# SuperSimpleEMG.net
KiCad netlist of a schematic drawn in EAGLE
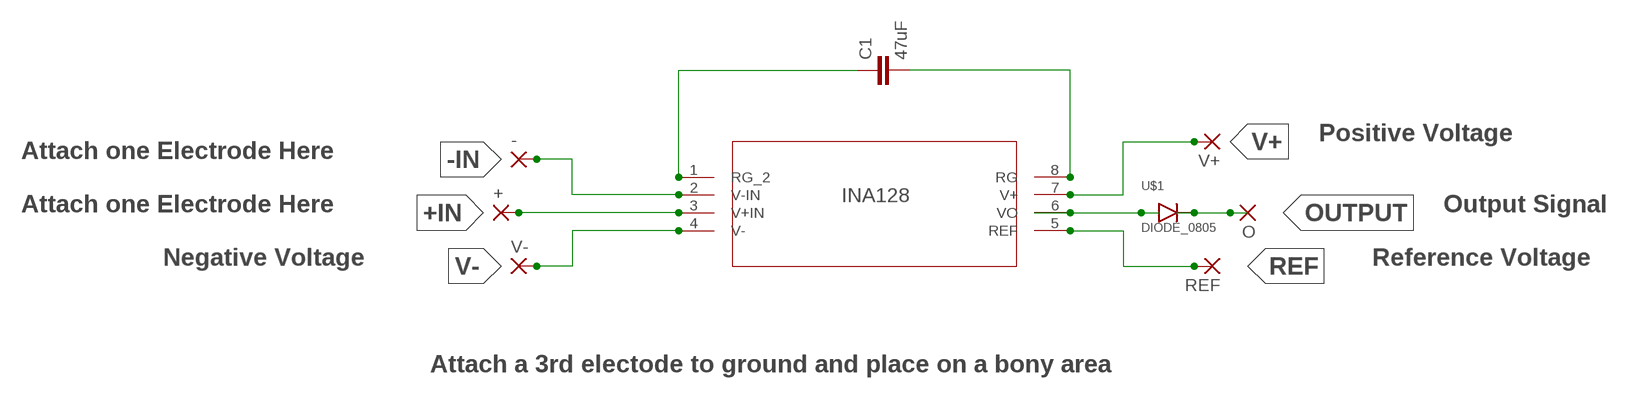
[diagram p0: schematic, sheet 1]

(export (version "E")
  (design (tool "Eeschema 10.0.6"))
  (components
    (comp (ref "+")
      (value "2,15/1,0")
      (footprint "eagle-import:2,15_1,0")
      (libsource (lib "eagle-import") (part "2,15/1,0"))
    )
    (comp (ref "-")
      (value "2,15/1,0")
      (footprint "eagle-import:2,15_1,0")
      (libsource (lib "eagle-import") (part "2,15/1,0"))
    )
    (comp (ref "C1")
      (value "47uF")
      (footprint "eagle-import:0805")
      (fields (field (name "MF") "NICHICON") (field (name "MPN") "F980J476MSA"))
      (libsource (lib "eagle-import") (part "CAP0805"))
    )
    (comp (ref "INA128")
      (value "INA128_D_8")
      (footprint "eagle-import:D8")
      (fields
        (field (name "GENERIC_PART_NUMBER") "INA128")
        (field (name "MANUFACTURER") "Texas Instruments")
        (field (name "MANUFACTURER_PART_NUMBER") "ina128_d_8")
      )
      (libsource (lib "eagle-import") (part "INA128_D_8"))
    )
    (comp (ref "O")
      (value "2,15/1,0")
      (footprint "eagle-import:2,15_1,0")
      (libsource (lib "eagle-import") (part "2,15/1,0"))
    )
    (comp (ref "REF")
      (value "2,15/1,0")
      (footprint "eagle-import:2,15_1,0")
      (libsource (lib "eagle-import") (part "2,15/1,0"))
    )
    (comp (ref "U$1")
      (value "DIODE_0805")
      (footprint "eagle-import:DIODE_0805")
      (libsource (lib "eagle-import") (part "DIODE_0805"))
    )
    (comp (ref "V+")
      (value "2,15/1,0")
      (footprint "eagle-import:2,15_1,0")
      (libsource (lib "eagle-import") (part "2,15/1,0"))
    )
    (comp (ref "V-")
      (value "2,15/1,0")
      (footprint "eagle-import:2,15_1,0")
      (libsource (lib "eagle-import") (part "2,15/1,0"))
    )
  )
  (nets
    (net (code "1") (name "+IN") (class "Default")
      (node (ref "+") (pin "1") (pinfunction "P_1") (pintype "passive"))
      (node (ref "INA128") (pin "3") (pinfunction "V+IN_3") (pintype "input"))
    )
    (net (code "2") (name "-IN") (class "Default")
      (node (ref "-") (pin "1") (pinfunction "P_1") (pintype "passive"))
      (node (ref "INA128") (pin "2") (pinfunction "V-IN_2") (pintype "input"))
    )
    (net (code "3") (name "Net-(INA128-RG)") (class "Default")
      (node (ref "C1") (pin "2") (pinfunction "2_2") (pintype "passive"))
      (node (ref "INA128") (pin "8") (pinfunction "RG_8") (pintype "passive"))
    )
    (net (code "4") (name "Net-(INA128-RG_2)") (class "Default")
      (node (ref "C1") (pin "1") (pinfunction "1_1") (pintype "passive"))
      (node (ref "INA128") (pin "1") (pinfunction "RG_2_1") (pintype "passive"))
    )
    (net (code "5") (name "Net-(INA128-VO)") (class "Default")
      (node (ref "INA128") (pin "6") (pinfunction "VO_6") (pintype "output"))
      (node (ref "U$1") (pin "A") (pinfunction "A_A") (pintype "passive"))
    )
    (net (code "6") (name "OUTPUT") (class "Default")
      (node (ref "O") (pin "1") (pinfunction "P_1") (pintype "passive"))
      (node (ref "U$1") (pin "C") (pinfunction "C_C") (pintype "passive"))
    )
    (net (code "7") (name "REF") (class "Default")
      (node (ref "INA128") (pin "5") (pinfunction "REF_5") (pintype "passive"))
      (node (ref "REF") (pin "1") (pinfunction "P_1") (pintype "passive"))
    )
    (net (code "8") (name "V+") (class "Default")
      (node (ref "INA128") (pin "7") (pinfunction "V+_7") (pintype "power_in"))
      (node (ref "V+") (pin "1") (pinfunction "P_1") (pintype "passive"))
    )
    (net (code "9") (name "V-") (class "Default")
      (node (ref "INA128") (pin "4") (pinfunction "V-_4") (pintype "power_in"))
      (node (ref "V-") (pin "1") (pinfunction "P_1") (pintype "passive"))
    )
  )
)
